# rev3-noserial.net
KiCad netlist of a schematic drawn in EAGLE
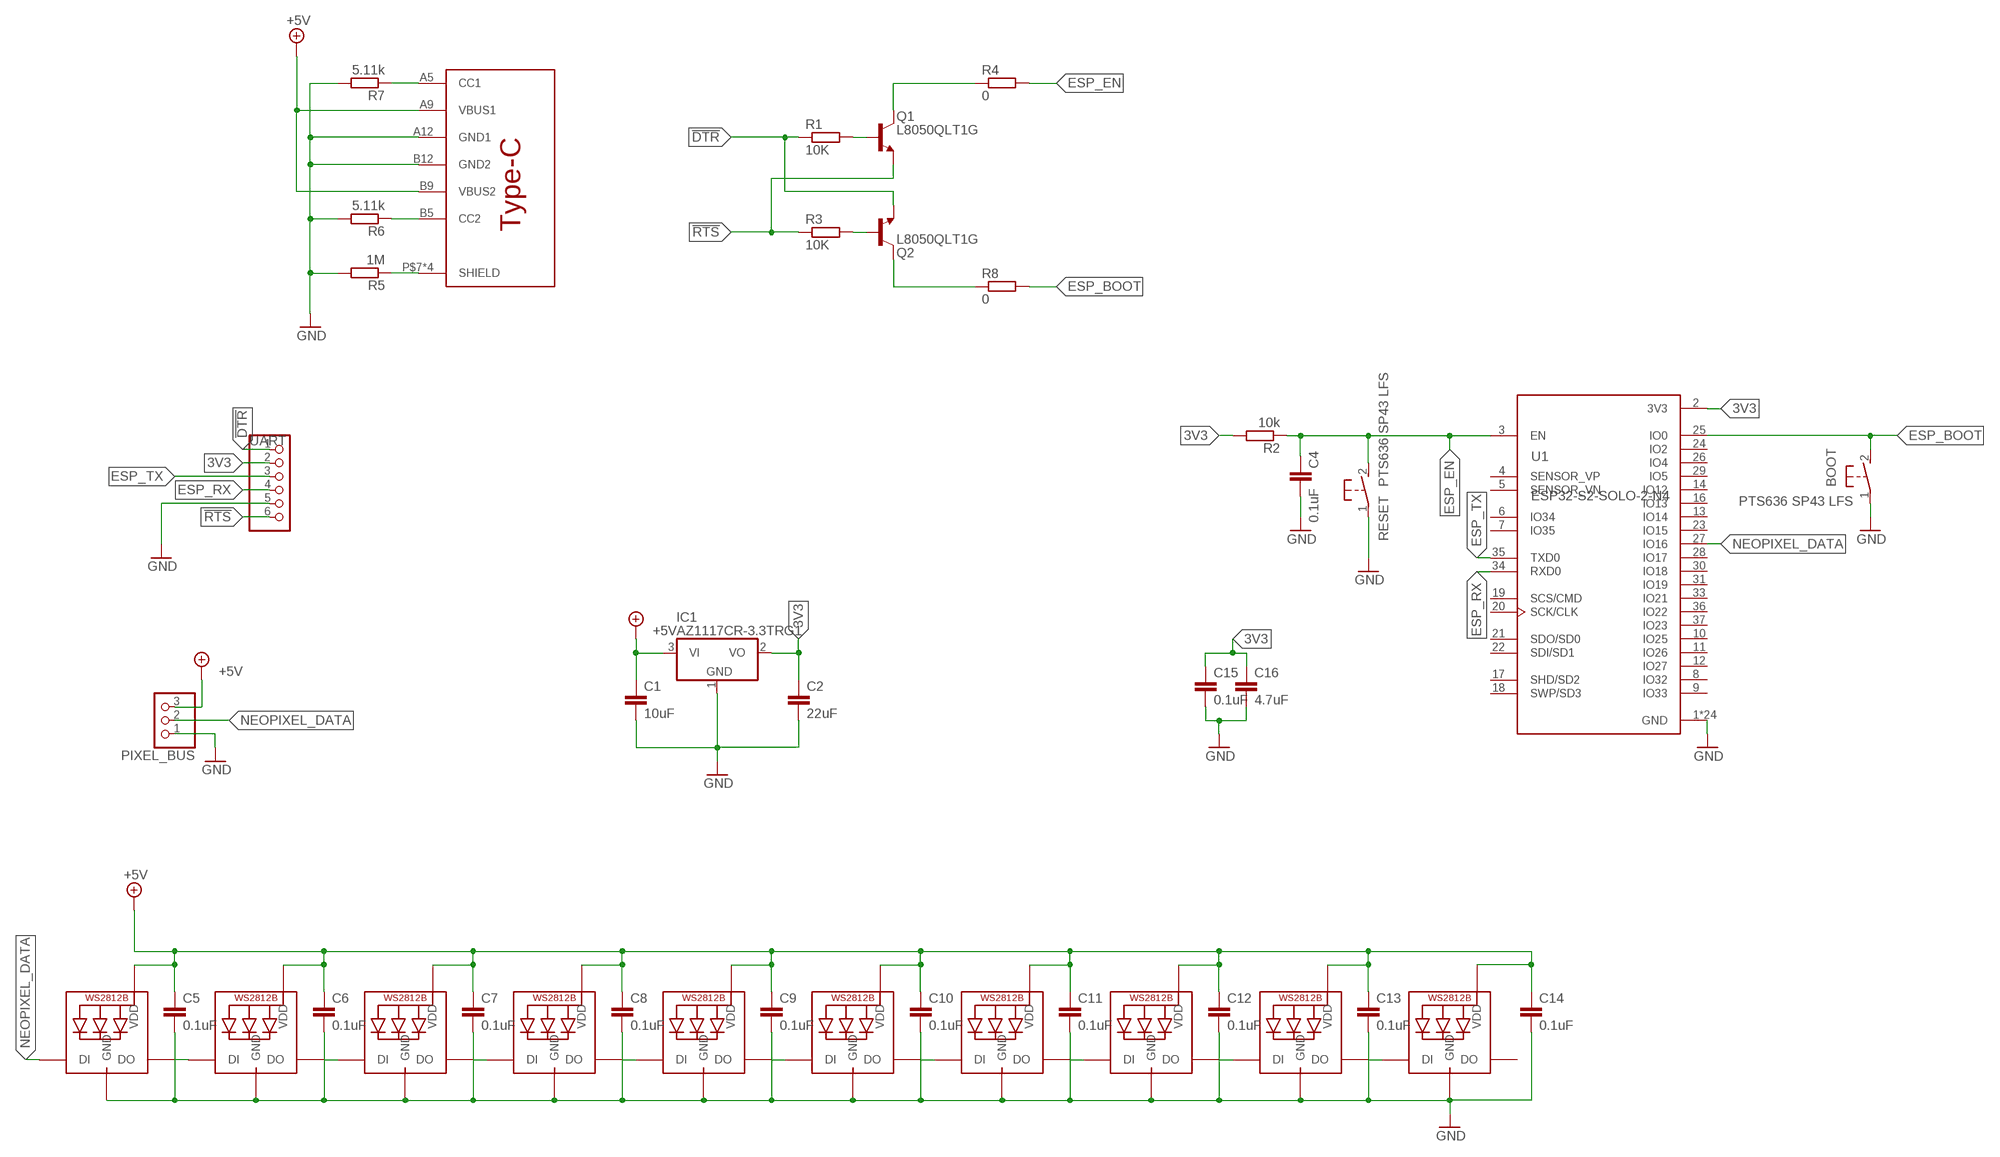
[diagram p0: schematic, sheet 1]

(export (version "E")
  (design (tool "Eeschema 10.0.6"))
  (components
    (comp (ref "BOOT")
      (value "PTS636 SP43 LFS")
      (footprint "eagle-import:PTS636SP43LFS")
      (libsource (lib "eagle-import") (part "PTS636SP43LFS"))
    )
    (comp (ref "C1")
      (value "10uF")
      (footprint "eagle-import:C0805")
      (libsource (lib "eagle-import") (part "C-EUC0805"))
    )
    (comp (ref "C2")
      (value "22uF")
      (footprint "eagle-import:C0805")
      (libsource (lib "eagle-import") (part "C-EUC0805"))
    )
    (comp (ref "C4")
      (value "0.1uF")
      (footprint "eagle-import:C0805")
      (libsource (lib "eagle-import") (part "C-EUC0805"))
    )
    (comp (ref "C5")
      (value "0.1uF")
      (footprint "eagle-import:C0805")
      (libsource (lib "eagle-import") (part "C-EUC0805"))
    )
    (comp (ref "C6")
      (value "0.1uF")
      (footprint "eagle-import:C0805")
      (libsource (lib "eagle-import") (part "C-EUC0805"))
    )
    (comp (ref "C7")
      (value "0.1uF")
      (footprint "eagle-import:C0805")
      (libsource (lib "eagle-import") (part "C-EUC0805"))
    )
    (comp (ref "C8")
      (value "0.1uF")
      (footprint "eagle-import:C0805")
      (libsource (lib "eagle-import") (part "C-EUC0805"))
    )
    (comp (ref "C9")
      (value "0.1uF")
      (footprint "eagle-import:C0805")
      (libsource (lib "eagle-import") (part "C-EUC0805"))
    )
    (comp (ref "C10")
      (value "0.1uF")
      (footprint "eagle-import:C0805")
      (libsource (lib "eagle-import") (part "C-EUC0805"))
    )
    (comp (ref "C11")
      (value "0.1uF")
      (footprint "eagle-import:C0805")
      (libsource (lib "eagle-import") (part "C-EUC0805"))
    )
    (comp (ref "C12")
      (value "0.1uF")
      (footprint "eagle-import:C0805")
      (libsource (lib "eagle-import") (part "C-EUC0805"))
    )
    (comp (ref "C13")
      (value "0.1uF")
      (footprint "eagle-import:C0805")
      (libsource (lib "eagle-import") (part "C-EUC0805"))
    )
    (comp (ref "C14")
      (value "0.1uF")
      (footprint "eagle-import:C0805")
      (libsource (lib "eagle-import") (part "C-EUC0805"))
    )
    (comp (ref "C15")
      (value "0.1uF")
      (footprint "eagle-import:C0805")
      (libsource (lib "eagle-import") (part "C-EUC0805"))
    )
    (comp (ref "C16")
      (value "4.7uF")
      (footprint "eagle-import:C0805")
      (libsource (lib "eagle-import") (part "C-EUC0805"))
    )
    (comp (ref "IC1")
      (value "AZ1117CR-3.3TRG1")
      (footprint "eagle-import:SOT89")
      (libsource (lib "eagle-import") (part "AZ1117CR"))
    )
    (comp (ref "LED1")
      (value "WS2812B5050")
      (footprint "eagle-import:WS2812B")
      (libsource (lib "eagle-import") (part "WS2812B5050"))
    )
    (comp (ref "LED2")
      (value "WS2812B5050")
      (footprint "eagle-import:WS2812B")
      (libsource (lib "eagle-import") (part "WS2812B5050"))
    )
    (comp (ref "LED3")
      (value "WS2812B5050")
      (footprint "eagle-import:WS2812B")
      (libsource (lib "eagle-import") (part "WS2812B5050"))
    )
    (comp (ref "LED4")
      (value "WS2812B5050")
      (footprint "eagle-import:WS2812B")
      (libsource (lib "eagle-import") (part "WS2812B5050"))
    )
    (comp (ref "LED5")
      (value "WS2812B5050")
      (footprint "eagle-import:WS2812B")
      (libsource (lib "eagle-import") (part "WS2812B5050"))
    )
    (comp (ref "LED6")
      (value "WS2812B5050")
      (footprint "eagle-import:WS2812B")
      (libsource (lib "eagle-import") (part "WS2812B5050"))
    )
    (comp (ref "LED7")
      (value "WS2812B5050")
      (footprint "eagle-import:WS2812B")
      (libsource (lib "eagle-import") (part "WS2812B5050"))
    )
    (comp (ref "LED8")
      (value "WS2812B5050")
      (footprint "eagle-import:WS2812B")
      (libsource (lib "eagle-import") (part "WS2812B5050"))
    )
    (comp (ref "LED9")
      (value "WS2812B5050")
      (footprint "eagle-import:WS2812B")
      (libsource (lib "eagle-import") (part "WS2812B5050"))
    )
    (comp (ref "LED10")
      (value "WS2812B5050")
      (footprint "eagle-import:WS2812B")
      (libsource (lib "eagle-import") (part "WS2812B5050"))
    )
    (comp (ref "PIXEL_BUS")
      (value "PINHD-1X3")
      (footprint "eagle-import:1X03")
      (libsource (lib "eagle-import") (part "PINHD-1X3"))
    )
    (comp (ref "Q1")
      (value "L8050QLT1G")
      (footprint "eagle-import:SOT95P237X112-3N")
      (fields (field (name "MANUFACTURER") "Nexperia USA Inc."))
      (libsource (lib "eagle-import") (part "NPN__SOT23-BECBC846A,215"))
    )
    (comp (ref "Q2")
      (value "L8050QLT1G")
      (footprint "eagle-import:SOT95P237X112-3N")
      (fields (field (name "MANUFACTURER") "Nexperia USA Inc."))
      (libsource (lib "eagle-import") (part "NPN__SOT23-BECBC846A,215"))
    )
    (comp (ref "R1")
      (value "10K")
      (footprint "eagle-import:R0805")
      (libsource (lib "eagle-import") (part "R-EU_R0805"))
    )
    (comp (ref "R2")
      (value "10k")
      (footprint "eagle-import:R0805")
      (libsource (lib "eagle-import") (part "R-EU_R0805"))
    )
    (comp (ref "R3")
      (value "10K")
      (footprint "eagle-import:R0805")
      (libsource (lib "eagle-import") (part "R-EU_R0805"))
    )
    (comp (ref "R4")
      (value "0")
      (footprint "eagle-import:R0805")
      (libsource (lib "eagle-import") (part "R-EU_R0805"))
    )
    (comp (ref "R5")
      (value "1M")
      (footprint "eagle-import:R0805")
      (libsource (lib "eagle-import") (part "R-EU_R0805"))
    )
    (comp (ref "R6")
      (value "5.11k")
      (footprint "eagle-import:R0805")
      (libsource (lib "eagle-import") (part "R-EU_R0805"))
    )
    (comp (ref "R7")
      (value "5.11k")
      (footprint "eagle-import:R0805")
      (libsource (lib "eagle-import") (part "R-EU_R0805"))
    )
    (comp (ref "R8")
      (value "0")
      (footprint "eagle-import:R0805")
      (libsource (lib "eagle-import") (part "R-EU_R0805"))
    )
    (comp (ref "RESET")
      (value "PTS636 SP43 LFS")
      (footprint "eagle-import:PTS636SP43LFS")
      (libsource (lib "eagle-import") (part "PTS636SP43LFS"))
    )
    (comp (ref "U$1")
      (value "TYPEC-DB-104PWB")
      (footprint "eagle-import:TYPEC-DB-104PWB")
      (fields (field (name "JLCPCBPART#") "C2936180"))
      (libsource (lib "eagle-import") (part "TYPEC-DB-104PWB"))
    )
    (comp (ref "U1")
      (value "ESP32-S2-SOLO-2-N4")
      (footprint "eagle-import:MODULE_ESP32-WROOM-32D")
      (fields (field (name "MF") "Espressif Systems") (field (name "MP") "ESP32-WROOM-32D"))
      (libsource (lib "eagle-import") (part "ESP32-WROOM-32D"))
    )
    (comp (ref "UART")
      (value "PINHD-1X6")
      (footprint "eagle-import:1X06")
      (libsource (lib "eagle-import") (part "PINHD-1X6"))
    )
  )
  (nets
    (net (code "1") (name "+5V") (class "Default")
      (node (ref "C1") (pin "1") (pinfunction "1_1") (pintype "passive"))
      (node (ref "C10") (pin "1") (pinfunction "1_1") (pintype "passive"))
      (node (ref "C11") (pin "1") (pinfunction "1_1") (pintype "passive"))
      (node (ref "C12") (pin "1") (pinfunction "1_1") (pintype "passive"))
      (node (ref "C13") (pin "1") (pinfunction "1_1") (pintype "passive"))
      (node (ref "C14") (pin "1") (pinfunction "1_1") (pintype "passive"))
      (node (ref "C5") (pin "1") (pinfunction "1_1") (pintype "passive"))
      (node (ref "C6") (pin "1") (pinfunction "1_1") (pintype "passive"))
      (node (ref "C7") (pin "1") (pinfunction "1_1") (pintype "passive"))
      (node (ref "C8") (pin "1") (pinfunction "1_1") (pintype "passive"))
      (node (ref "C9") (pin "1") (pinfunction "1_1") (pintype "passive"))
      (node (ref "IC1") (pin "3") (pinfunction "VI_3") (pintype "input"))
      (node (ref "LED1") (pin "1-VDD") (pinfunction "VDD_1-VDD") (pintype "power_in"))
      (node (ref "LED10") (pin "1-VDD") (pinfunction "VDD_1-VDD") (pintype "power_in"))
      (node (ref "LED2") (pin "1-VDD") (pinfunction "VDD_1-VDD") (pintype "power_in"))
      (node (ref "LED3") (pin "1-VDD") (pinfunction "VDD_1-VDD") (pintype "power_in"))
      (node (ref "LED4") (pin "1-VDD") (pinfunction "VDD_1-VDD") (pintype "power_in"))
      (node (ref "LED5") (pin "1-VDD") (pinfunction "VDD_1-VDD") (pintype "power_in"))
      (node (ref "LED6") (pin "1-VDD") (pinfunction "VDD_1-VDD") (pintype "power_in"))
      (node (ref "LED7") (pin "1-VDD") (pinfunction "VDD_1-VDD") (pintype "power_in"))
      (node (ref "LED8") (pin "1-VDD") (pinfunction "VDD_1-VDD") (pintype "power_in"))
      (node (ref "LED9") (pin "1-VDD") (pinfunction "VDD_1-VDD") (pintype "power_in"))
      (node (ref "PIXEL_BUS") (pin "3") (pinfunction "3_3") (pintype "passive"))
      (node (ref "U$1") (pin "A9") (pinfunction "VBUS1_A9") (pintype "bidirectional"))
      (node (ref "U$1") (pin "B9") (pinfunction "VBUS2_B9") (pintype "bidirectional"))
    )
    (net (code "2") (name "/~{DTR}") (class "Default")
      (node (ref "Q2") (pin "2") (pinfunction "E_2") (pintype "passive"))
      (node (ref "R1") (pin "1") (pinfunction "1_1") (pintype "passive"))
      (node (ref "UART") (pin "1") (pinfunction "1_1") (pintype "passive"))
    )
    (net (code "3") (name "/~{RTS}") (class "Default")
      (node (ref "Q1") (pin "2") (pinfunction "E_2") (pintype "passive"))
      (node (ref "R3") (pin "1") (pinfunction "1_1") (pintype "passive"))
      (node (ref "UART") (pin "6") (pinfunction "6_6") (pintype "passive"))
    )
    (net (code "4") (name "3V3") (class "Default")
      (node (ref "C15") (pin "1") (pinfunction "1_1") (pintype "passive"))
      (node (ref "C16") (pin "1") (pinfunction "1_1") (pintype "passive"))
      (node (ref "C2") (pin "1") (pinfunction "1_1") (pintype "passive"))
      (node (ref "IC1") (pin "2") (pinfunction "VO_2") (pintype "passive"))
      (node (ref "R2") (pin "2") (pinfunction "2_2") (pintype "passive"))
      (node (ref "U1") (pin "2") (pinfunction "3V3_2") (pintype "power_in"))
      (node (ref "UART") (pin "2") (pinfunction "2_2") (pintype "passive"))
    )
    (net (code "5") (name "ESP_BOOT") (class "Default")
      (node (ref "BOOT") (pin "2") (pinfunction "2_2") (pintype "passive"))
      (node (ref "R8") (pin "2") (pinfunction "2_2") (pintype "passive"))
      (node (ref "U1") (pin "25") (pinfunction "IO0_25") (pintype "bidirectional"))
    )
    (net (code "6") (name "ESP_EN") (class "Default")
      (node (ref "C4") (pin "1") (pinfunction "1_1") (pintype "passive"))
      (node (ref "R2") (pin "1") (pinfunction "1_1") (pintype "passive"))
      (node (ref "R4") (pin "2") (pinfunction "2_2") (pintype "passive"))
      (node (ref "RESET") (pin "2") (pinfunction "2_2") (pintype "passive"))
      (node (ref "U1") (pin "3") (pinfunction "EN_3") (pintype "input"))
    )
    (net (code "7") (name "ESP_RX") (class "Default")
      (node (ref "U1") (pin "34") (pinfunction "RXD0_34") (pintype "bidirectional"))
      (node (ref "UART") (pin "4") (pinfunction "4_4") (pintype "passive"))
    )
    (net (code "8") (name "ESP_TX") (class "Default")
      (node (ref "U1") (pin "35") (pinfunction "TXD0_35") (pintype "bidirectional"))
      (node (ref "UART") (pin "3") (pinfunction "3_3") (pintype "passive"))
    )
    (net (code "9") (name "GND") (class "Default")
      (node (ref "BOOT") (pin "1") (pinfunction "1_1") (pintype "passive"))
      (node (ref "C1") (pin "2") (pinfunction "2_2") (pintype "passive"))
      (node (ref "C10") (pin "2") (pinfunction "2_2") (pintype "passive"))
      (node (ref "C11") (pin "2") (pinfunction "2_2") (pintype "passive"))
      (node (ref "C12") (pin "2") (pinfunction "2_2") (pintype "passive"))
      (node (ref "C13") (pin "2") (pinfunction "2_2") (pintype "passive"))
      (node (ref "C14") (pin "2") (pinfunction "2_2") (pintype "passive"))
      (node (ref "C15") (pin "2") (pinfunction "2_2") (pintype "passive"))
      (node (ref "C16") (pin "2") (pinfunction "2_2") (pintype "passive"))
      (node (ref "C2") (pin "2") (pinfunction "2_2") (pintype "passive"))
      (node (ref "C4") (pin "2") (pinfunction "2_2") (pintype "passive"))
      (node (ref "C5") (pin "2") (pinfunction "2_2") (pintype "passive"))
      (node (ref "C6") (pin "2") (pinfunction "2_2") (pintype "passive"))
      (node (ref "C7") (pin "2") (pinfunction "2_2") (pintype "passive"))
      (node (ref "C8") (pin "2") (pinfunction "2_2") (pintype "passive"))
      (node (ref "C9") (pin "2") (pinfunction "2_2") (pintype "passive"))
      (node (ref "IC1") (pin "1") (pinfunction "GND_1") (pintype "passive"))
      (node (ref "LED1") (pin "3-GND") (pinfunction "GND_3-GND") (pintype "power_in"))
      (node (ref "LED10") (pin "3-GND") (pinfunction "GND_3-GND") (pintype "power_in"))
      (node (ref "LED2") (pin "3-GND") (pinfunction "GND_3-GND") (pintype "power_in"))
      (node (ref "LED3") (pin "3-GND") (pinfunction "GND_3-GND") (pintype "power_in"))
      (node (ref "LED4") (pin "3-GND") (pinfunction "GND_3-GND") (pintype "power_in"))
      (node (ref "LED5") (pin "3-GND") (pinfunction "GND_3-GND") (pintype "power_in"))
      (node (ref "LED6") (pin "3-GND") (pinfunction "GND_3-GND") (pintype "power_in"))
      (node (ref "LED7") (pin "3-GND") (pinfunction "GND_3-GND") (pintype "power_in"))
      (node (ref "LED8") (pin "3-GND") (pinfunction "GND_3-GND") (pintype "power_in"))
      (node (ref "LED9") (pin "3-GND") (pinfunction "GND_3-GND") (pintype "power_in"))
      (node (ref "PIXEL_BUS") (pin "1") (pinfunction "1_1") (pintype "passive"))
      (node (ref "R5") (pin "2") (pinfunction "2_2") (pintype "passive"))
      (node (ref "R6") (pin "2") (pinfunction "2_2") (pintype "passive"))
      (node (ref "R7") (pin "2") (pinfunction "2_2") (pintype "passive"))
      (node (ref "RESET") (pin "1") (pinfunction "1_1") (pintype "passive"))
      (node (ref "U$1") (pin "A12") (pinfunction "GND1_A12") (pintype "bidirectional"))
      (node (ref "U$1") (pin "B12") (pinfunction "GND2_B12") (pintype "bidirectional"))
      (node (ref "U1") (pin "1") (pinfunction "GND_1") (pintype "power_in"))
      (node (ref "U1") (pin "15") (pinfunction "GND_15") (pintype "power_in"))
      (node (ref "U1") (pin "38") (pinfunction "GND_38") (pintype "power_in"))
      (node (ref "U1") (pin "39_1") (pinfunction "GND_39_1") (pintype "power_in"))
      (node (ref "U1") (pin "39_10") (pinfunction "GND_39_10") (pintype "power_in"))
      (node (ref "U1") (pin "39_11") (pinfunction "GND_39_11") (pintype "power_in"))
      (node (ref "U1") (pin "39_12") (pinfunction "GND_39_12") (pintype "power_in"))
      (node (ref "U1") (pin "39_13") (pinfunction "GND_39_13") (pintype "power_in"))
      (node (ref "U1") (pin "39_14") (pinfunction "GND_39_14") (pintype "power_in"))
      (node (ref "U1") (pin "39_15") (pinfunction "GND_39_15") (pintype "power_in"))
      (node (ref "U1") (pin "39_16") (pinfunction "GND_39_16") (pintype "power_in"))
      (node (ref "U1") (pin "39_17") (pinfunction "GND_39_17") (pintype "power_in"))
      (node (ref "U1") (pin "39_18") (pinfunction "GND_39_18") (pintype "power_in"))
      (node (ref "U1") (pin "39_19") (pinfunction "GND_39_19") (pintype "power_in"))
      (node (ref "U1") (pin "39_2") (pinfunction "GND_39_2") (pintype "power_in"))
      (node (ref "U1") (pin "39_20") (pinfunction "GND_39_20") (pintype "power_in"))
      (node (ref "U1") (pin "39_21") (pinfunction "GND_39_21") (pintype "power_in"))
      (node (ref "U1") (pin "39_3") (pinfunction "GND_39_3") (pintype "power_in"))
      (node (ref "U1") (pin "39_4") (pinfunction "GND_39_4") (pintype "power_in"))
      (node (ref "U1") (pin "39_5") (pinfunction "GND_39_5") (pintype "power_in"))
      (node (ref "U1") (pin "39_6") (pinfunction "GND_39_6") (pintype "power_in"))
      (node (ref "U1") (pin "39_7") (pinfunction "GND_39_7") (pintype "power_in"))
      (node (ref "U1") (pin "39_8") (pinfunction "GND_39_8") (pintype "power_in"))
      (node (ref "U1") (pin "39_9") (pinfunction "GND_39_9") (pintype "power_in"))
      (node (ref "UART") (pin "5") (pinfunction "5_5") (pintype "passive"))
    )
    (net (code "10") (name "NEOPIXEL_DATA") (class "Default")
      (node (ref "LED1") (pin "4-DIN") (pinfunction "DI_4-DIN") (pintype "input"))
      (node (ref "PIXEL_BUS") (pin "2") (pinfunction "2_2") (pintype "passive"))
      (node (ref "U1") (pin "27") (pinfunction "IO16_27") (pintype "bidirectional"))
    )
    (net (code "11") (name "Net-(LED1-DO)") (class "Default")
      (node (ref "LED1") (pin "2-DOUT") (pinfunction "DO_2-DOUT") (pintype "output"))
      (node (ref "LED2") (pin "4-DIN") (pinfunction "DI_4-DIN") (pintype "input"))
    )
    (net (code "12") (name "Net-(LED2-DO)") (class "Default")
      (node (ref "LED2") (pin "2-DOUT") (pinfunction "DO_2-DOUT") (pintype "output"))
      (node (ref "LED3") (pin "4-DIN") (pinfunction "DI_4-DIN") (pintype "input"))
    )
    (net (code "13") (name "Net-(LED3-DO)") (class "Default")
      (node (ref "LED3") (pin "2-DOUT") (pinfunction "DO_2-DOUT") (pintype "output"))
      (node (ref "LED4") (pin "4-DIN") (pinfunction "DI_4-DIN") (pintype "input"))
    )
    (net (code "14") (name "Net-(LED4-DO)") (class "Default")
      (node (ref "LED4") (pin "2-DOUT") (pinfunction "DO_2-DOUT") (pintype "output"))
      (node (ref "LED5") (pin "4-DIN") (pinfunction "DI_4-DIN") (pintype "input"))
    )
    (net (code "15") (name "Net-(LED5-DO)") (class "Default")
      (node (ref "LED5") (pin "2-DOUT") (pinfunction "DO_2-DOUT") (pintype "output"))
      (node (ref "LED6") (pin "4-DIN") (pinfunction "DI_4-DIN") (pintype "input"))
    )
    (net (code "16") (name "Net-(LED6-DO)") (class "Default")
      (node (ref "LED6") (pin "2-DOUT") (pinfunction "DO_2-DOUT") (pintype "output"))
      (node (ref "LED7") (pin "4-DIN") (pinfunction "DI_4-DIN") (pintype "input"))
    )
    (net (code "17") (name "Net-(LED7-DO)") (class "Default")
      (node (ref "LED7") (pin "2-DOUT") (pinfunction "DO_2-DOUT") (pintype "output"))
      (node (ref "LED8") (pin "4-DIN") (pinfunction "DI_4-DIN") (pintype "input"))
    )
    (net (code "18") (name "Net-(LED8-DO)") (class "Default")
      (node (ref "LED8") (pin "2-DOUT") (pinfunction "DO_2-DOUT") (pintype "output"))
      (node (ref "LED9") (pin "4-DIN") (pinfunction "DI_4-DIN") (pintype "input"))
    )
    (net (code "19") (name "Net-(LED10-DI)") (class "Default")
      (node (ref "LED10") (pin "4-DIN") (pinfunction "DI_4-DIN") (pintype "input"))
      (node (ref "LED9") (pin "2-DOUT") (pinfunction "DO_2-DOUT") (pintype "output"))
    )
    (net (code "20") (name "Net-(Q1-B)") (class "Default")
      (node (ref "Q1") (pin "1") (pinfunction "B_1") (pintype "passive"))
      (node (ref "R1") (pin "2") (pinfunction "2_2") (pintype "passive"))
    )
    (net (code "21") (name "Net-(Q1-C)") (class "Default")
      (node (ref "Q1") (pin "3") (pinfunction "C_3") (pintype "passive"))
      (node (ref "R4") (pin "1") (pinfunction "1_1") (pintype "passive"))
    )
    (net (code "22") (name "Net-(Q2-B)") (class "Default")
      (node (ref "Q2") (pin "1") (pinfunction "B_1") (pintype "passive"))
      (node (ref "R3") (pin "2") (pinfunction "2_2") (pintype "passive"))
    )
    (net (code "23") (name "Net-(Q2-C)") (class "Default")
      (node (ref "Q2") (pin "3") (pinfunction "C_3") (pintype "passive"))
      (node (ref "R8") (pin "1") (pinfunction "1_1") (pintype "passive"))
    )
    (net (code "24") (name "Net-(R5-Pad1)") (class "Default")
      (node (ref "R5") (pin "1") (pinfunction "1_1") (pintype "passive"))
      (node (ref "U$1") (pin "P$10") (pinfunction "SHIELD_P$10") (pintype "bidirectional"))
      (node (ref "U$1") (pin "P$7") (pinfunction "SHIELD_P$7") (pintype "bidirectional"))
      (node (ref "U$1") (pin "P$8") (pinfunction "SHIELD_P$8") (pintype "bidirectional"))
      (node (ref "U$1") (pin "P$9") (pinfunction "SHIELD_P$9") (pintype "bidirectional"))
    )
    (net (code "25") (name "Net-(U$1-CC1)") (class "Default")
      (node (ref "R7") (pin "1") (pinfunction "1_1") (pintype "passive"))
      (node (ref "U$1") (pin "A5") (pinfunction "CC1_A5") (pintype "bidirectional"))
    )
    (net (code "26") (name "Net-(U$1-CC2)") (class "Default")
      (node (ref "R6") (pin "1") (pinfunction "1_1") (pintype "passive"))
      (node (ref "U$1") (pin "B5") (pinfunction "CC2_B5") (pintype "bidirectional"))
    )
    (net (code "27") (name "unconnected-(LED10-DO-Pad2-DOUT)") (class "Default")
      (node (ref "LED10") (pin "2-DOUT") (pinfunction "DO_2-DOUT") (pintype "output"))
    )
    (net (code "28") (name "unconnected-(U1-IO2-Pad24)") (class "Default")
      (node (ref "U1") (pin "24") (pinfunction "IO2_24") (pintype "bidirectional"))
    )
    (net (code "29") (name "unconnected-(U1-IO4-Pad26)") (class "Default")
      (node (ref "U1") (pin "26") (pinfunction "IO4_26") (pintype "bidirectional"))
    )
    (net (code "30") (name "unconnected-(U1-IO5-Pad29)") (class "Default")
      (node (ref "U1") (pin "29") (pinfunction "IO5_29") (pintype "bidirectional"))
    )
    (net (code "31") (name "unconnected-(U1-IO12-Pad14)") (class "Default")
      (node (ref "U1") (pin "14") (pinfunction "IO12_14") (pintype "bidirectional"))
    )
    (net (code "32") (name "unconnected-(U1-IO13-Pad16)") (class "Default")
      (node (ref "U1") (pin "16") (pinfunction "IO13_16") (pintype "bidirectional"))
    )
    (net (code "33") (name "unconnected-(U1-IO14-Pad13)") (class "Default")
      (node (ref "U1") (pin "13") (pinfunction "IO14_13") (pintype "bidirectional"))
    )
    (net (code "34") (name "unconnected-(U1-IO15-Pad23)") (class "Default")
      (node (ref "U1") (pin "23") (pinfunction "IO15_23") (pintype "bidirectional"))
    )
    (net (code "35") (name "unconnected-(U1-IO17-Pad28)") (class "Default")
      (node (ref "U1") (pin "28") (pinfunction "IO17_28") (pintype "bidirectional"))
    )
    (net (code "36") (name "unconnected-(U1-IO18-Pad30)") (class "Default")
      (node (ref "U1") (pin "30") (pinfunction "IO18_30") (pintype "bidirectional"))
    )
    (net (code "37") (name "unconnected-(U1-IO19-Pad31)") (class "Default")
      (node (ref "U1") (pin "31") (pinfunction "IO19_31") (pintype "bidirectional"))
    )
    (net (code "38") (name "unconnected-(U1-IO21-Pad33)") (class "Default")
      (node (ref "U1") (pin "33") (pinfunction "IO21_33") (pintype "bidirectional"))
    )
    (net (code "39") (name "unconnected-(U1-IO22-Pad36)") (class "Default")
      (node (ref "U1") (pin "36") (pinfunction "IO22_36") (pintype "bidirectional"))
    )
    (net (code "40") (name "unconnected-(U1-IO23-Pad37)") (class "Default")
      (node (ref "U1") (pin "37") (pinfunction "IO23_37") (pintype "bidirectional"))
    )
    (net (code "41") (name "unconnected-(U1-IO25-Pad10)") (class "Default")
      (node (ref "U1") (pin "10") (pinfunction "IO25_10") (pintype "bidirectional"))
    )
    (net (code "42") (name "unconnected-(U1-IO26-Pad11)") (class "Default")
      (node (ref "U1") (pin "11") (pinfunction "IO26_11") (pintype "bidirectional"))
    )
    (net (code "43") (name "unconnected-(U1-IO27-Pad12)") (class "Default")
      (node (ref "U1") (pin "12") (pinfunction "IO27_12") (pintype "bidirectional"))
    )
    (net (code "44") (name "unconnected-(U1-IO32-Pad8)") (class "Default")
      (node (ref "U1") (pin "8") (pinfunction "IO32_8") (pintype "bidirectional"))
    )
    (net (code "45") (name "unconnected-(U1-IO33-Pad9)") (class "Default")
      (node (ref "U1") (pin "9") (pinfunction "IO33_9") (pintype "bidirectional"))
    )
    (net (code "46") (name "unconnected-(U1-IO34-Pad6)") (class "Default")
      (node (ref "U1") (pin "6") (pinfunction "IO34_6") (pintype "input"))
    )
    (net (code "47") (name "unconnected-(U1-IO35-Pad7)") (class "Default")
      (node (ref "U1") (pin "7") (pinfunction "IO35_7") (pintype "input"))
    )
    (net (code "48") (name "unconnected-(U1-SCK{slash}CLK-Pad20)") (class "Default")
      (node (ref "U1") (pin "20") (pinfunction "SCK/CLK_20") (pintype "bidirectional"))
    )
    (net (code "49") (name "unconnected-(U1-SCS{slash}CMD-Pad19)") (class "Default")
      (node (ref "U1") (pin "19") (pinfunction "SCS/CMD_19") (pintype "bidirectional"))
    )
    (net (code "50") (name "unconnected-(U1-SDI{slash}SD1-Pad22)") (class "Default")
      (node (ref "U1") (pin "22") (pinfunction "SDI/SD1_22") (pintype "bidirectional"))
    )
    (net (code "51") (name "unconnected-(U1-SDO{slash}SD0-Pad21)") (class "Default")
      (node (ref "U1") (pin "21") (pinfunction "SDO/SD0_21") (pintype "bidirectional"))
    )
    (net (code "52") (name "unconnected-(U1-SENSOR_VN-Pad5)") (class "Default")
      (node (ref "U1") (pin "5") (pinfunction "SENSOR_VN_5") (pintype "input"))
    )
    (net (code "53") (name "unconnected-(U1-SENSOR_VP-Pad4)") (class "Default")
      (node (ref "U1") (pin "4") (pinfunction "SENSOR_VP_4") (pintype "input"))
    )
    (net (code "54") (name "unconnected-(U1-SHD{slash}SD2-Pad17)") (class "Default")
      (node (ref "U1") (pin "17") (pinfunction "SHD/SD2_17") (pintype "bidirectional"))
    )
    (net (code "55") (name "unconnected-(U1-SWP{slash}SD3-Pad18)") (class "Default")
      (node (ref "U1") (pin "18") (pinfunction "SWP/SD3_18") (pintype "bidirectional"))
    )
  )
)
